# Extension_Board.net
KiCad netlist of a schematic drawn in EAGLE
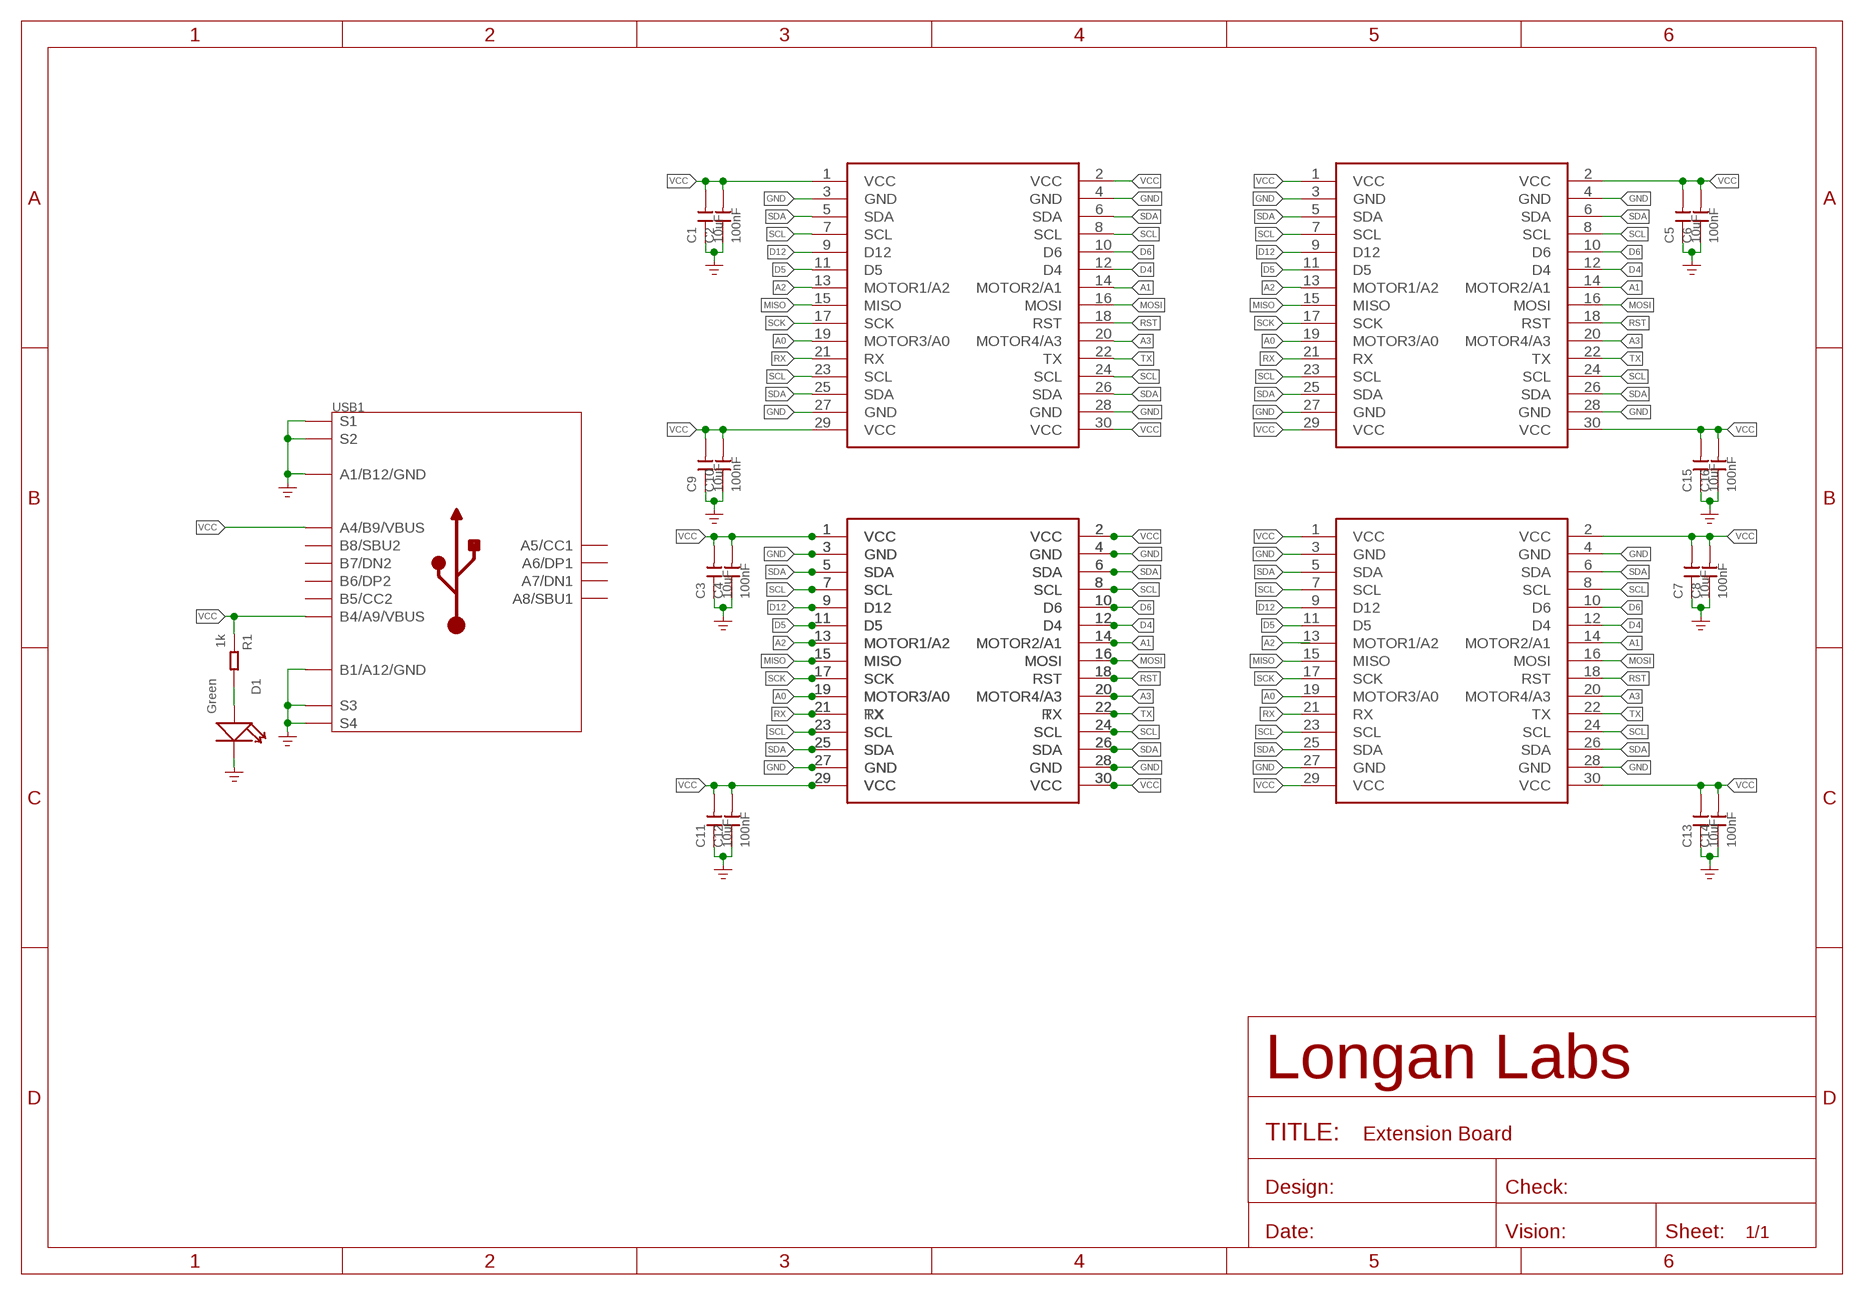
[diagram p0: schematic, sheet 1]

(export (version "E")
  (design (tool "Eeschema 10.0.6"))
  (components
    (comp (ref "C1")
      (value "10uF")
      (footprint "eagle-import:C0603")
      (libsource (lib "eagle-import") (part "CAP-0603"))
    )
    (comp (ref "C2")
      (value "100nF")
      (footprint "eagle-import:C0603")
      (libsource (lib "eagle-import") (part "CAP-0603"))
    )
    (comp (ref "C3")
      (value "10uF")
      (footprint "eagle-import:C0603")
      (libsource (lib "eagle-import") (part "CAP-0603"))
    )
    (comp (ref "C4")
      (value "100nF")
      (footprint "eagle-import:C0603")
      (libsource (lib "eagle-import") (part "CAP-0603"))
    )
    (comp (ref "C5")
      (value "10uF")
      (footprint "eagle-import:C0603")
      (libsource (lib "eagle-import") (part "CAP-0603"))
    )
    (comp (ref "C6")
      (value "100nF")
      (footprint "eagle-import:C0603")
      (libsource (lib "eagle-import") (part "CAP-0603"))
    )
    (comp (ref "C7")
      (value "10uF")
      (footprint "eagle-import:C0603")
      (libsource (lib "eagle-import") (part "CAP-0603"))
    )
    (comp (ref "C8")
      (value "100nF")
      (footprint "eagle-import:C0603")
      (libsource (lib "eagle-import") (part "CAP-0603"))
    )
    (comp (ref "C9")
      (value "10uF")
      (footprint "eagle-import:C0603")
      (libsource (lib "eagle-import") (part "CAP-0603"))
    )
    (comp (ref "C10")
      (value "100nF")
      (footprint "eagle-import:C0603")
      (libsource (lib "eagle-import") (part "CAP-0603"))
    )
    (comp (ref "C11")
      (value "10uF")
      (footprint "eagle-import:C0603")
      (libsource (lib "eagle-import") (part "CAP-0603"))
    )
    (comp (ref "C12")
      (value "100nF")
      (footprint "eagle-import:C0603")
      (libsource (lib "eagle-import") (part "CAP-0603"))
    )
    (comp (ref "C13")
      (value "10uF")
      (footprint "eagle-import:C0603")
      (libsource (lib "eagle-import") (part "CAP-0603"))
    )
    (comp (ref "C14")
      (value "100nF")
      (footprint "eagle-import:C0603")
      (libsource (lib "eagle-import") (part "CAP-0603"))
    )
    (comp (ref "C15")
      (value "10uF")
      (footprint "eagle-import:C0603")
      (libsource (lib "eagle-import") (part "CAP-0603"))
    )
    (comp (ref "C16")
      (value "100nF")
      (footprint "eagle-import:C0603")
      (libsource (lib "eagle-import") (part "CAP-0603"))
    )
    (comp (ref "D1")
      (value "Green")
      (footprint "eagle-import:LED-0603")
      (libsource (lib "eagle-import") (part "LED'0603'"))
    )
    (comp (ref "MOUDLE1")
      (value "MOUDLE-2X15P-2.54'2.54'")
      (footprint "eagle-import:2X15P-2.54")
      (libsource (lib "eagle-import") (part "MOUDLE-2X15P-2.54'2.54'"))
    )
    (comp (ref "MOUDLE2")
      (value "MOUDLE-2X15P-2.54'2.54'")
      (footprint "eagle-import:2X15P-2.54")
      (libsource (lib "eagle-import") (part "MOUDLE-2X15P-2.54'2.54'"))
    )
    (comp (ref "MOUDLE3")
      (value "MOUDLE-2X15P-2.54'2.54'")
      (footprint "eagle-import:2X15P-2.54")
      (libsource (lib "eagle-import") (part "MOUDLE-2X15P-2.54'2.54'"))
    )
    (comp (ref "MOUDLE4")
      (value "MOUDLE-2X15P-2.54'90D'")
      (footprint "eagle-import:2X15P-2.54-90D")
      (libsource (lib "eagle-import") (part "MOUDLE-2X15P-2.54'90D'"))
    )
    (comp (ref "MOUDLE5")
      (value "MOUDLE-2X15P-2.54-PAD'BOARD'")
      (footprint "eagle-import:MOUDLE-2X15P-2.54")
      (libsource (lib "eagle-import") (part "MOUDLE-2X15P-2.54-PAD'BOARD'"))
    )
    (comp (ref "R1")
      (value "1k")
      (footprint "eagle-import:R0603")
      (libsource (lib "eagle-import") (part "RES-0603"))
    )
    (comp (ref "USB1")
      (value "USB2.0-TYPE-C")
      (footprint "eagle-import:USB2.0-TYPE-C")
      (libsource (lib "eagle-import") (part "USB2.0-TYPE-C"))
    )
  )
  (nets
    (net (code "1") (name "A0") (class "Default")
      (node (ref "MOUDLE1") (pin "19") (pinfunction "MOTOR3/A0_19") (pintype "bidirectional"))
      (node (ref "MOUDLE2") (pin "19") (pinfunction "MOTOR3/A0_19") (pintype "bidirectional"))
      (node (ref "MOUDLE3") (pin "19") (pinfunction "MOTOR3/A0_19") (pintype "bidirectional"))
      (node (ref "MOUDLE4") (pin "19") (pinfunction "MOTOR3/A0_19") (pintype "bidirectional"))
      (node (ref "MOUDLE5") (pin "19") (pinfunction "MOTOR3/A0_19") (pintype "bidirectional"))
    )
    (net (code "2") (name "A1") (class "Default")
      (node (ref "MOUDLE1") (pin "14") (pinfunction "MOTOR2/A1_14") (pintype "bidirectional"))
      (node (ref "MOUDLE2") (pin "14") (pinfunction "MOTOR2/A1_14") (pintype "bidirectional"))
      (node (ref "MOUDLE3") (pin "14") (pinfunction "MOTOR2/A1_14") (pintype "bidirectional"))
      (node (ref "MOUDLE4") (pin "14") (pinfunction "MOTOR2/A1_14") (pintype "bidirectional"))
      (node (ref "MOUDLE5") (pin "14") (pinfunction "MOTOR2/A1_14") (pintype "bidirectional"))
    )
    (net (code "3") (name "A2") (class "Default")
      (node (ref "MOUDLE1") (pin "13") (pinfunction "MOTOR1/A2_13") (pintype "bidirectional"))
      (node (ref "MOUDLE2") (pin "13") (pinfunction "MOTOR1/A2_13") (pintype "bidirectional"))
      (node (ref "MOUDLE4") (pin "13") (pinfunction "MOTOR1/A2_13") (pintype "bidirectional"))
      (node (ref "MOUDLE5") (pin "13") (pinfunction "MOTOR1/A2_13") (pintype "bidirectional"))
    )
    (net (code "4") (name "A3") (class "Default")
      (node (ref "MOUDLE1") (pin "20") (pinfunction "MOTOR4/A3_20") (pintype "bidirectional"))
      (node (ref "MOUDLE2") (pin "20") (pinfunction "MOTOR4/A3_20") (pintype "bidirectional"))
      (node (ref "MOUDLE3") (pin "20") (pinfunction "MOTOR4/A3_20") (pintype "bidirectional"))
      (node (ref "MOUDLE4") (pin "20") (pinfunction "MOTOR4/A3_20") (pintype "bidirectional"))
      (node (ref "MOUDLE5") (pin "20") (pinfunction "MOTOR4/A3_20") (pintype "bidirectional"))
    )
    (net (code "5") (name "D4") (class "Default")
      (node (ref "MOUDLE1") (pin "12") (pinfunction "D4_12") (pintype "bidirectional"))
      (node (ref "MOUDLE2") (pin "12") (pinfunction "D4_12") (pintype "bidirectional"))
      (node (ref "MOUDLE3") (pin "12") (pinfunction "D4_12") (pintype "bidirectional"))
      (node (ref "MOUDLE4") (pin "12") (pinfunction "D4_12") (pintype "bidirectional"))
      (node (ref "MOUDLE5") (pin "12") (pinfunction "D4_12") (pintype "bidirectional"))
    )
    (net (code "6") (name "D5") (class "Default")
      (node (ref "MOUDLE1") (pin "11") (pinfunction "D5_11") (pintype "bidirectional"))
      (node (ref "MOUDLE2") (pin "11") (pinfunction "D5_11") (pintype "bidirectional"))
      (node (ref "MOUDLE3") (pin "11") (pinfunction "D5_11") (pintype "bidirectional"))
      (node (ref "MOUDLE4") (pin "11") (pinfunction "D5_11") (pintype "bidirectional"))
      (node (ref "MOUDLE5") (pin "11") (pinfunction "D5_11") (pintype "bidirectional"))
    )
    (net (code "7") (name "D6") (class "Default")
      (node (ref "MOUDLE1") (pin "10") (pinfunction "D6_10") (pintype "bidirectional"))
      (node (ref "MOUDLE2") (pin "10") (pinfunction "D6_10") (pintype "bidirectional"))
      (node (ref "MOUDLE3") (pin "10") (pinfunction "D6_10") (pintype "bidirectional"))
      (node (ref "MOUDLE4") (pin "10") (pinfunction "D6_10") (pintype "bidirectional"))
      (node (ref "MOUDLE5") (pin "10") (pinfunction "D6_10") (pintype "bidirectional"))
    )
    (net (code "8") (name "D12") (class "Default")
      (node (ref "MOUDLE1") (pin "9") (pinfunction "D12_9") (pintype "bidirectional"))
      (node (ref "MOUDLE2") (pin "9") (pinfunction "D12_9") (pintype "bidirectional"))
      (node (ref "MOUDLE3") (pin "9") (pinfunction "D12_9") (pintype "bidirectional"))
      (node (ref "MOUDLE4") (pin "9") (pinfunction "D12_9") (pintype "bidirectional"))
      (node (ref "MOUDLE5") (pin "9") (pinfunction "D12_9") (pintype "bidirectional"))
    )
    (net (code "9") (name "GND") (class "Default")
      (node (ref "C1") (pin "1") (pinfunction "1_1") (pintype "passive"))
      (node (ref "C10") (pin "1") (pinfunction "1_1") (pintype "passive"))
      (node (ref "C11") (pin "1") (pinfunction "1_1") (pintype "passive"))
      (node (ref "C12") (pin "1") (pinfunction "1_1") (pintype "passive"))
      (node (ref "C13") (pin "1") (pinfunction "1_1") (pintype "passive"))
      (node (ref "C14") (pin "1") (pinfunction "1_1") (pintype "passive"))
      (node (ref "C15") (pin "1") (pinfunction "1_1") (pintype "passive"))
      (node (ref "C16") (pin "1") (pinfunction "1_1") (pintype "passive"))
      (node (ref "C2") (pin "1") (pinfunction "1_1") (pintype "passive"))
      (node (ref "C3") (pin "1") (pinfunction "1_1") (pintype "passive"))
      (node (ref "C4") (pin "1") (pinfunction "1_1") (pintype "passive"))
      (node (ref "C5") (pin "1") (pinfunction "1_1") (pintype "passive"))
      (node (ref "C6") (pin "1") (pinfunction "1_1") (pintype "passive"))
      (node (ref "C7") (pin "1") (pinfunction "1_1") (pintype "passive"))
      (node (ref "C8") (pin "1") (pinfunction "1_1") (pintype "passive"))
      (node (ref "C9") (pin "1") (pinfunction "1_1") (pintype "passive"))
      (node (ref "D1") (pin "-") (pinfunction "-_-") (pintype "passive"))
      (node (ref "MOUDLE1") (pin "27") (pinfunction "GND_27") (pintype "bidirectional"))
      (node (ref "MOUDLE1") (pin "28") (pinfunction "GND_28") (pintype "bidirectional"))
      (node (ref "MOUDLE1") (pin "3") (pinfunction "GND_3") (pintype "bidirectional"))
      (node (ref "MOUDLE1") (pin "4") (pinfunction "GND_4") (pintype "bidirectional"))
      (node (ref "MOUDLE2") (pin "27") (pinfunction "GND_27") (pintype "bidirectional"))
      (node (ref "MOUDLE2") (pin "28") (pinfunction "GND_28") (pintype "bidirectional"))
      (node (ref "MOUDLE2") (pin "3") (pinfunction "GND_3") (pintype "bidirectional"))
      (node (ref "MOUDLE2") (pin "4") (pinfunction "GND_4") (pintype "bidirectional"))
      (node (ref "MOUDLE3") (pin "27") (pinfunction "GND_27") (pintype "bidirectional"))
      (node (ref "MOUDLE3") (pin "28") (pinfunction "GND_28") (pintype "bidirectional"))
      (node (ref "MOUDLE3") (pin "3") (pinfunction "GND_3") (pintype "bidirectional"))
      (node (ref "MOUDLE3") (pin "4") (pinfunction "GND_4") (pintype "bidirectional"))
      (node (ref "MOUDLE4") (pin "27") (pinfunction "GND_27") (pintype "bidirectional"))
      (node (ref "MOUDLE4") (pin "28") (pinfunction "GND_28") (pintype "bidirectional"))
      (node (ref "MOUDLE4") (pin "3") (pinfunction "GND_3") (pintype "bidirectional"))
      (node (ref "MOUDLE4") (pin "4") (pinfunction "GND_4") (pintype "bidirectional"))
      (node (ref "MOUDLE5") (pin "27") (pinfunction "GND_27") (pintype "bidirectional"))
      (node (ref "MOUDLE5") (pin "28") (pinfunction "GND_28") (pintype "bidirectional"))
      (node (ref "MOUDLE5") (pin "3") (pinfunction "GND_3") (pintype "bidirectional"))
      (node (ref "MOUDLE5") (pin "4") (pinfunction "GND_4") (pintype "bidirectional"))
      (node (ref "USB1") (pin "A1_B12") (pinfunction "A1/B12/GND_A1_B12") (pintype "bidirectional"))
      (node (ref "USB1") (pin "B1_A12") (pinfunction "B1/A12/GND_B1_A12") (pintype "bidirectional"))
      (node (ref "USB1") (pin "S1") (pinfunction "S1_S1") (pintype "bidirectional"))
      (node (ref "USB1") (pin "S2") (pinfunction "S2_S2") (pintype "bidirectional"))
      (node (ref "USB1") (pin "S3") (pinfunction "S3_S3") (pintype "bidirectional"))
      (node (ref "USB1") (pin "S4") (pinfunction "S4_S4") (pintype "bidirectional"))
      (node (ref "USB1") (pin "S5") (pinfunction "S1_S5") (pintype "bidirectional"))
      (node (ref "USB1") (pin "S6") (pinfunction "S2_S6") (pintype "bidirectional"))
    )
    (net (code "10") (name "MISO") (class "Default")
      (node (ref "MOUDLE1") (pin "15") (pinfunction "MISO_15") (pintype "bidirectional"))
      (node (ref "MOUDLE2") (pin "15") (pinfunction "MISO_15") (pintype "bidirectional"))
      (node (ref "MOUDLE3") (pin "15") (pinfunction "MISO_15") (pintype "bidirectional"))
      (node (ref "MOUDLE4") (pin "15") (pinfunction "MISO_15") (pintype "bidirectional"))
      (node (ref "MOUDLE5") (pin "15") (pinfunction "MISO_15") (pintype "bidirectional"))
    )
    (net (code "11") (name "MOSI") (class "Default")
      (node (ref "MOUDLE1") (pin "16") (pinfunction "MOSI_16") (pintype "bidirectional"))
      (node (ref "MOUDLE2") (pin "16") (pinfunction "MOSI_16") (pintype "bidirectional"))
      (node (ref "MOUDLE3") (pin "16") (pinfunction "MOSI_16") (pintype "bidirectional"))
      (node (ref "MOUDLE4") (pin "16") (pinfunction "MOSI_16") (pintype "bidirectional"))
      (node (ref "MOUDLE5") (pin "16") (pinfunction "MOSI_16") (pintype "bidirectional"))
    )
    (net (code "12") (name "Net-(D1-Pad+)") (class "Default")
      (node (ref "D1") (pin "+") (pinfunction "+_+") (pintype "passive"))
      (node (ref "R1") (pin "2") (pinfunction "2_2") (pintype "passive"))
    )
    (net (code "13") (name "RST") (class "Default")
      (node (ref "MOUDLE1") (pin "18") (pinfunction "RST_18") (pintype "bidirectional"))
      (node (ref "MOUDLE2") (pin "18") (pinfunction "RST_18") (pintype "bidirectional"))
      (node (ref "MOUDLE3") (pin "18") (pinfunction "RST_18") (pintype "bidirectional"))
      (node (ref "MOUDLE4") (pin "18") (pinfunction "RST_18") (pintype "bidirectional"))
      (node (ref "MOUDLE5") (pin "18") (pinfunction "RST_18") (pintype "bidirectional"))
    )
    (net (code "14") (name "RX") (class "Default")
      (node (ref "MOUDLE1") (pin "21") (pinfunction "RX_21") (pintype "bidirectional"))
      (node (ref "MOUDLE2") (pin "21") (pinfunction "RX_21") (pintype "bidirectional"))
      (node (ref "MOUDLE3") (pin "21") (pinfunction "RX_21") (pintype "bidirectional"))
      (node (ref "MOUDLE4") (pin "21") (pinfunction "RX_21") (pintype "bidirectional"))
      (node (ref "MOUDLE5") (pin "21") (pinfunction "TX_21") (pintype "bidirectional"))
    )
    (net (code "15") (name "SCK") (class "Default")
      (node (ref "MOUDLE1") (pin "17") (pinfunction "SCK_17") (pintype "bidirectional"))
      (node (ref "MOUDLE2") (pin "17") (pinfunction "SCK_17") (pintype "bidirectional"))
      (node (ref "MOUDLE3") (pin "17") (pinfunction "SCK_17") (pintype "bidirectional"))
      (node (ref "MOUDLE4") (pin "17") (pinfunction "SCK_17") (pintype "bidirectional"))
      (node (ref "MOUDLE5") (pin "17") (pinfunction "SCK_17") (pintype "bidirectional"))
    )
    (net (code "16") (name "SCL") (class "Default")
      (node (ref "MOUDLE1") (pin "23") (pinfunction "SCL_23") (pintype "bidirectional"))
      (node (ref "MOUDLE1") (pin "24") (pinfunction "SCL_24") (pintype "bidirectional"))
      (node (ref "MOUDLE1") (pin "7") (pinfunction "SCL_7") (pintype "bidirectional"))
      (node (ref "MOUDLE1") (pin "8") (pinfunction "SCL_8") (pintype "bidirectional"))
      (node (ref "MOUDLE2") (pin "23") (pinfunction "SCL_23") (pintype "bidirectional"))
      (node (ref "MOUDLE2") (pin "24") (pinfunction "SCL_24") (pintype "bidirectional"))
      (node (ref "MOUDLE2") (pin "7") (pinfunction "SCL_7") (pintype "bidirectional"))
      (node (ref "MOUDLE2") (pin "8") (pinfunction "SCL_8") (pintype "bidirectional"))
      (node (ref "MOUDLE3") (pin "23") (pinfunction "SCL_23") (pintype "bidirectional"))
      (node (ref "MOUDLE3") (pin "24") (pinfunction "SCL_24") (pintype "bidirectional"))
      (node (ref "MOUDLE3") (pin "7") (pinfunction "SCL_7") (pintype "bidirectional"))
      (node (ref "MOUDLE3") (pin "8") (pinfunction "SCL_8") (pintype "bidirectional"))
      (node (ref "MOUDLE4") (pin "23") (pinfunction "SCL_23") (pintype "bidirectional"))
      (node (ref "MOUDLE4") (pin "24") (pinfunction "SCL_24") (pintype "bidirectional"))
      (node (ref "MOUDLE4") (pin "7") (pinfunction "SCL_7") (pintype "bidirectional"))
      (node (ref "MOUDLE4") (pin "8") (pinfunction "SCL_8") (pintype "bidirectional"))
      (node (ref "MOUDLE5") (pin "23") (pinfunction "SCL_23") (pintype "bidirectional"))
      (node (ref "MOUDLE5") (pin "24") (pinfunction "SCL_24") (pintype "bidirectional"))
      (node (ref "MOUDLE5") (pin "7") (pinfunction "SCL_7") (pintype "bidirectional"))
      (node (ref "MOUDLE5") (pin "8") (pinfunction "SCL_8") (pintype "bidirectional"))
    )
    (net (code "17") (name "SDA") (class "Default")
      (node (ref "MOUDLE1") (pin "25") (pinfunction "SDA_25") (pintype "bidirectional"))
      (node (ref "MOUDLE1") (pin "26") (pinfunction "SDA_26") (pintype "bidirectional"))
      (node (ref "MOUDLE1") (pin "5") (pinfunction "SDA_5") (pintype "bidirectional"))
      (node (ref "MOUDLE1") (pin "6") (pinfunction "SDA_6") (pintype "bidirectional"))
      (node (ref "MOUDLE2") (pin "25") (pinfunction "SDA_25") (pintype "bidirectional"))
      (node (ref "MOUDLE2") (pin "26") (pinfunction "SDA_26") (pintype "bidirectional"))
      (node (ref "MOUDLE2") (pin "5") (pinfunction "SDA_5") (pintype "bidirectional"))
      (node (ref "MOUDLE2") (pin "6") (pinfunction "SDA_6") (pintype "bidirectional"))
      (node (ref "MOUDLE3") (pin "25") (pinfunction "SDA_25") (pintype "bidirectional"))
      (node (ref "MOUDLE3") (pin "26") (pinfunction "SDA_26") (pintype "bidirectional"))
      (node (ref "MOUDLE3") (pin "5") (pinfunction "SDA_5") (pintype "bidirectional"))
      (node (ref "MOUDLE3") (pin "6") (pinfunction "SDA_6") (pintype "bidirectional"))
      (node (ref "MOUDLE4") (pin "25") (pinfunction "SDA_25") (pintype "bidirectional"))
      (node (ref "MOUDLE4") (pin "26") (pinfunction "SDA_26") (pintype "bidirectional"))
      (node (ref "MOUDLE4") (pin "5") (pinfunction "SDA_5") (pintype "bidirectional"))
      (node (ref "MOUDLE4") (pin "6") (pinfunction "SDA_6") (pintype "bidirectional"))
      (node (ref "MOUDLE5") (pin "25") (pinfunction "SDA_25") (pintype "bidirectional"))
      (node (ref "MOUDLE5") (pin "26") (pinfunction "SDA_26") (pintype "bidirectional"))
      (node (ref "MOUDLE5") (pin "5") (pinfunction "SDA_5") (pintype "bidirectional"))
      (node (ref "MOUDLE5") (pin "6") (pinfunction "SDA_6") (pintype "bidirectional"))
    )
    (net (code "18") (name "TX") (class "Default")
      (node (ref "MOUDLE1") (pin "22") (pinfunction "TX_22") (pintype "bidirectional"))
      (node (ref "MOUDLE2") (pin "22") (pinfunction "TX_22") (pintype "bidirectional"))
      (node (ref "MOUDLE3") (pin "22") (pinfunction "TX_22") (pintype "bidirectional"))
      (node (ref "MOUDLE4") (pin "22") (pinfunction "TX_22") (pintype "bidirectional"))
      (node (ref "MOUDLE5") (pin "22") (pinfunction "RX_22") (pintype "bidirectional"))
    )
    (net (code "19") (name "VCC") (class "Default")
      (node (ref "C1") (pin "2") (pinfunction "2_2") (pintype "passive"))
      (node (ref "C10") (pin "2") (pinfunction "2_2") (pintype "passive"))
      (node (ref "C11") (pin "2") (pinfunction "2_2") (pintype "passive"))
      (node (ref "C12") (pin "2") (pinfunction "2_2") (pintype "passive"))
      (node (ref "C13") (pin "2") (pinfunction "2_2") (pintype "passive"))
      (node (ref "C14") (pin "2") (pinfunction "2_2") (pintype "passive"))
      (node (ref "C15") (pin "2") (pinfunction "2_2") (pintype "passive"))
      (node (ref "C16") (pin "2") (pinfunction "2_2") (pintype "passive"))
      (node (ref "C2") (pin "2") (pinfunction "2_2") (pintype "passive"))
      (node (ref "C3") (pin "2") (pinfunction "2_2") (pintype "passive"))
      (node (ref "C4") (pin "2") (pinfunction "2_2") (pintype "passive"))
      (node (ref "C5") (pin "2") (pinfunction "2_2") (pintype "passive"))
      (node (ref "C6") (pin "2") (pinfunction "2_2") (pintype "passive"))
      (node (ref "C7") (pin "2") (pinfunction "2_2") (pintype "passive"))
      (node (ref "C8") (pin "2") (pinfunction "2_2") (pintype "passive"))
      (node (ref "C9") (pin "2") (pinfunction "2_2") (pintype "passive"))
      (node (ref "MOUDLE1") (pin "1") (pinfunction "VCC_1") (pintype "bidirectional"))
      (node (ref "MOUDLE1") (pin "2") (pinfunction "VCC_2") (pintype "bidirectional"))
      (node (ref "MOUDLE1") (pin "29") (pinfunction "VCC_29") (pintype "bidirectional"))
      (node (ref "MOUDLE1") (pin "30") (pinfunction "VCC_30") (pintype "bidirectional"))
      (node (ref "MOUDLE2") (pin "1") (pinfunction "VCC_1") (pintype "bidirectional"))
      (node (ref "MOUDLE2") (pin "2") (pinfunction "VCC_2") (pintype "bidirectional"))
      (node (ref "MOUDLE2") (pin "29") (pinfunction "VCC_29") (pintype "bidirectional"))
      (node (ref "MOUDLE2") (pin "30") (pinfunction "VCC_30") (pintype "bidirectional"))
      (node (ref "MOUDLE3") (pin "1") (pinfunction "VCC_1") (pintype "bidirectional"))
      (node (ref "MOUDLE3") (pin "2") (pinfunction "VCC_2") (pintype "bidirectional"))
      (node (ref "MOUDLE3") (pin "29") (pinfunction "VCC_29") (pintype "bidirectional"))
      (node (ref "MOUDLE3") (pin "30") (pinfunction "VCC_30") (pintype "bidirectional"))
      (node (ref "MOUDLE4") (pin "1") (pinfunction "VCC_1") (pintype "bidirectional"))
      (node (ref "MOUDLE4") (pin "2") (pinfunction "VCC_2") (pintype "bidirectional"))
      (node (ref "MOUDLE4") (pin "29") (pinfunction "VCC_29") (pintype "bidirectional"))
      (node (ref "MOUDLE4") (pin "30") (pinfunction "VCC_30") (pintype "bidirectional"))
      (node (ref "MOUDLE5") (pin "1") (pinfunction "VCC_1") (pintype "bidirectional"))
      (node (ref "MOUDLE5") (pin "2") (pinfunction "VCC_2") (pintype "bidirectional"))
      (node (ref "MOUDLE5") (pin "29") (pinfunction "VCC_29") (pintype "bidirectional"))
      (node (ref "MOUDLE5") (pin "30") (pinfunction "VCC_30") (pintype "bidirectional"))
      (node (ref "R1") (pin "1") (pinfunction "1_1") (pintype "passive"))
      (node (ref "USB1") (pin "A4_B9") (pinfunction "A4/B9/VBUS_A4_B9") (pintype "bidirectional"))
      (node (ref "USB1") (pin "B4_A9") (pinfunction "B4/A9/VBUS_B4_A9") (pintype "bidirectional"))
    )
    (net (code "20") (name "unconnected-(MOUDLE3-MOTOR1{slash}A2-Pad13)") (class "Default")
      (node (ref "MOUDLE3") (pin "13") (pinfunction "MOTOR1/A2_13") (pintype "bidirectional"))
    )
    (net (code "21") (name "unconnected-(USB1-A5{slash}CC1-PadA5)") (class "Default")
      (node (ref "USB1") (pin "A5") (pinfunction "A5/CC1_A5") (pintype "bidirectional"))
    )
    (net (code "22") (name "unconnected-(USB1-A6{slash}DP1-PadA6)") (class "Default")
      (node (ref "USB1") (pin "A6") (pinfunction "A6/DP1_A6") (pintype "bidirectional"))
    )
    (net (code "23") (name "unconnected-(USB1-A7{slash}DN1-PadA7)") (class "Default")
      (node (ref "USB1") (pin "A7") (pinfunction "A7/DN1_A7") (pintype "bidirectional"))
    )
    (net (code "24") (name "unconnected-(USB1-A8{slash}SBU1-PadA8)") (class "Default")
      (node (ref "USB1") (pin "A8") (pinfunction "A8/SBU1_A8") (pintype "bidirectional"))
    )
    (net (code "25") (name "unconnected-(USB1-B5{slash}CC2-PadB5)") (class "Default")
      (node (ref "USB1") (pin "B5") (pinfunction "B5/CC2_B5") (pintype "bidirectional"))
    )
    (net (code "26") (name "unconnected-(USB1-B6{slash}DP2-PadB6)") (class "Default")
      (node (ref "USB1") (pin "B6") (pinfunction "B6/DP2_B6") (pintype "bidirectional"))
    )
    (net (code "27") (name "unconnected-(USB1-B7{slash}DN2-PadB7)") (class "Default")
      (node (ref "USB1") (pin "B7") (pinfunction "B7/DN2_B7") (pintype "bidirectional"))
    )
    (net (code "28") (name "unconnected-(USB1-B8{slash}SBU2-PadB8)") (class "Default")
      (node (ref "USB1") (pin "B8") (pinfunction "B8/SBU2_B8") (pintype "bidirectional"))
    )
  )
)
